# Effect_SCH.net
KiCad netlist of a schematic drawn in Altium Designer
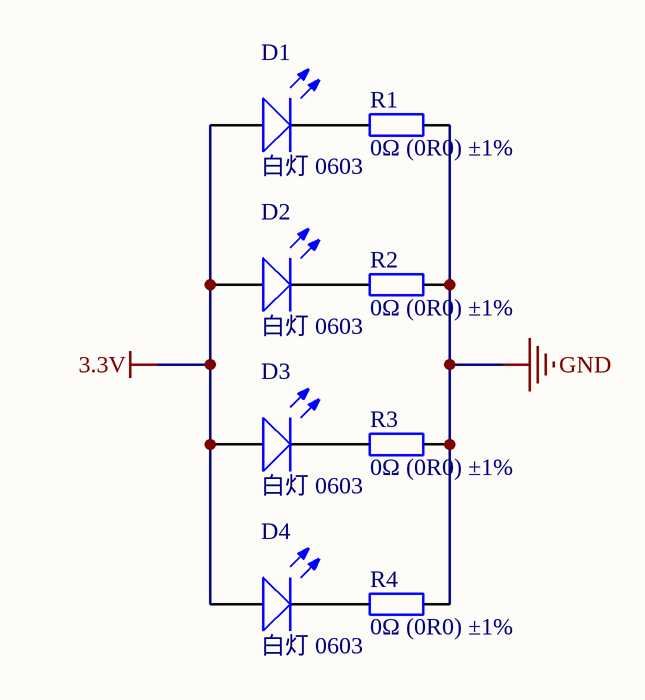
[diagram p0: Effect_SCH.SchDoc]

(export (version "E")
  (design (tool "Eeschema 10.0.6"))
  (components
    (comp (ref "D1")
      (value "白灯 0603")
      (footprint "0603_LED_S1")
      (description "发光二极管")
      (libsource (lib "Miscellaneous Devices LC") (part "0603 白灯"))
    )
    (comp (ref "D2")
      (value "白灯 0603")
      (footprint "0603_LED_S1")
      (description "发光二极管")
      (libsource (lib "Miscellaneous Devices LC") (part "0603 白灯"))
    )
    (comp (ref "D3")
      (value "白灯 0603")
      (footprint "0603_LED_S1")
      (description "发光二极管")
      (libsource (lib "Miscellaneous Devices LC") (part "0603 白灯"))
    )
    (comp (ref "D4")
      (value "白灯 0603")
      (footprint "0603_LED_S1")
      (description "发光二极管")
      (libsource (lib "Miscellaneous Devices LC") (part "0603 白灯"))
    )
    (comp (ref "R1")
      (value "0Ω (0R0) ±1%")
      (footprint "0603_R")
      (description "贴片电阻")
      (libsource (lib "Miscellaneous Devices LC") (part "0603 0Ω (0R0) 1%"))
    )
    (comp (ref "R2")
      (value "0Ω (0R0) ±1%")
      (footprint "0603_R")
      (description "贴片电阻")
      (libsource (lib "Miscellaneous Devices LC") (part "0603 0Ω (0R0) 1%"))
    )
    (comp (ref "R3")
      (value "0Ω (0R0) ±1%")
      (footprint "0603_R")
      (description "贴片电阻")
      (libsource (lib "Miscellaneous Devices LC") (part "0603 0Ω (0R0) 1%"))
    )
    (comp (ref "R4")
      (value "0Ω (0R0) ±1%")
      (footprint "0603_R")
      (description "贴片电阻")
      (libsource (lib "Miscellaneous Devices LC") (part "0603 0Ω (0R0) 1%"))
    )
  )
  (nets
    (net (code "1") (name "3.3V") (class "Default")
      (node (ref "D1") (pin "A") (pinfunction "A_A") (pintype "passive"))
      (node (ref "D2") (pin "A") (pinfunction "A_A") (pintype "passive"))
      (node (ref "D3") (pin "A") (pinfunction "A_A") (pintype "passive"))
      (node (ref "D4") (pin "A") (pinfunction "A_A") (pintype "passive"))
    )
    (net (code "2") (name "GND") (class "Default")
      (node (ref "R1") (pin "2") (pinfunction "2_2") (pintype "passive"))
      (node (ref "R2") (pin "2") (pinfunction "2_2") (pintype "passive"))
      (node (ref "R3") (pin "2") (pinfunction "2_2") (pintype "passive"))
      (node (ref "R4") (pin "2") (pinfunction "2_2") (pintype "passive"))
    )
    (net (code "3") (name "Net-(D1-PadK)") (class "Default")
      (node (ref "D1") (pin "K") (pinfunction "K_K") (pintype "passive"))
      (node (ref "R1") (pin "1") (pinfunction "1_1") (pintype "passive"))
    )
    (net (code "4") (name "Net-(D2-PadK)") (class "Default")
      (node (ref "D2") (pin "K") (pinfunction "K_K") (pintype "passive"))
      (node (ref "R2") (pin "1") (pinfunction "1_1") (pintype "passive"))
    )
    (net (code "5") (name "Net-(D3-PadK)") (class "Default")
      (node (ref "D3") (pin "K") (pinfunction "K_K") (pintype "passive"))
      (node (ref "R3") (pin "1") (pinfunction "1_1") (pintype "passive"))
    )
    (net (code "6") (name "Net-(D4-PadK)") (class "Default")
      (node (ref "D4") (pin "K") (pinfunction "K_K") (pintype "passive"))
      (node (ref "R4") (pin "1") (pinfunction "1_1") (pintype "passive"))
    )
  )
)
